# esp8266_env.net
KiCad netlist of a schematic drawn in EAGLE
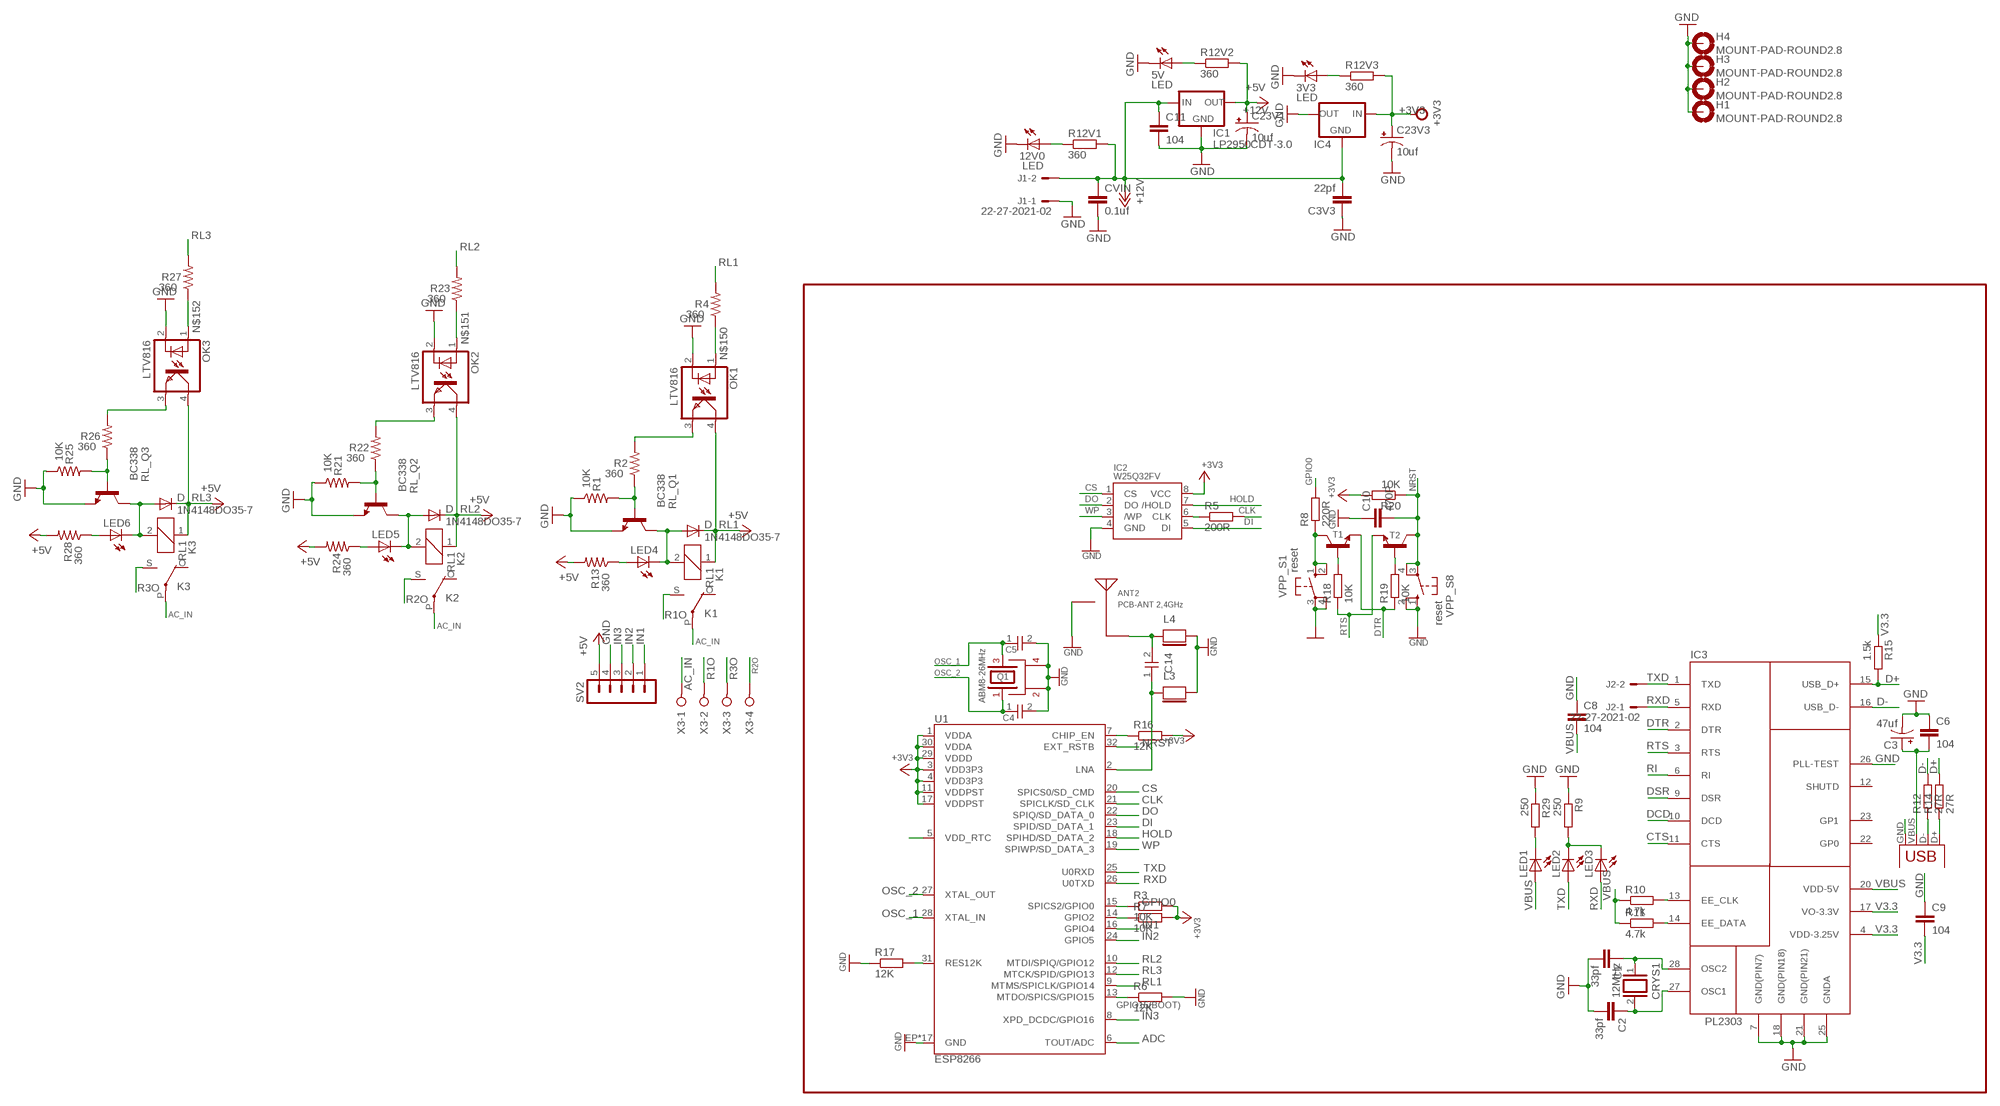
[diagram p0: schematic, sheet 1]

(export (version "E")
  (design (tool "Eeschema 10.0.6"))
  (components
    (comp (ref "3V3")
      (value "LED")
      (footprint "eagle-import:SML0805")
      (libsource (lib "eagle-import") (part "LEDSML0805"))
    )
    (comp (ref "5V")
      (value "LED")
      (footprint "eagle-import:SML0805")
      (libsource (lib "eagle-import") (part "LEDSML0805"))
    )
    (comp (ref "12V0")
      (value "LED")
      (footprint "eagle-import:SML0805")
      (libsource (lib "eagle-import") (part "LEDSML0805"))
    )
    (comp (ref "ANT2")
      (value "PCB-ANT 2,4GHz")
      (footprint "eagle-import:2.4GHZ_PCB")
      (libsource (lib "eagle-import") (part "2.4GHZ_PCB"))
    )
    (comp (ref "C1")
      (value "33pf")
      (footprint "eagle-import:C0805")
      (libsource (lib "eagle-import") (part "C-EUC0805"))
    )
    (comp (ref "C2")
      (value "33pf")
      (footprint "eagle-import:C0805")
      (libsource (lib "eagle-import") (part "C-EUC0805"))
    )
    (comp (ref "C3")
      (value "47uf")
      (footprint "eagle-import:E2,5-5")
      (libsource (lib "eagle-import") (part "CPOL-USE2.5-5"))
    )
    (comp (ref "C3V3")
      (value "22pf")
      (footprint "eagle-import:C0805")
      (libsource (lib "eagle-import") (part "C-EUC0805"))
    )
    (comp (ref "C4")
      (value "10P-50VCOG_0603")
      (footprint "eagle-import:C0603")
      (libsource (lib "eagle-import") (part "COG?_060310P-50V"))
    )
    (comp (ref "C5")
      (value "10P-50VCOG_0603")
      (footprint "eagle-import:C0603")
      (libsource (lib "eagle-import") (part "COG?_060310P-50V"))
    )
    (comp (ref "C6")
      (value "104")
      (footprint "eagle-import:C0805")
      (libsource (lib "eagle-import") (part "C-EUC0805"))
    )
    (comp (ref "C8")
      (value "104")
      (footprint "eagle-import:C0805")
      (libsource (lib "eagle-import") (part "C-EUC0805"))
    )
    (comp (ref "C9")
      (value "104")
      (footprint "eagle-import:C0805")
      (libsource (lib "eagle-import") (part "C-EUC0805"))
    )
    (comp (ref "C10")
      (value "470P")
      (footprint "eagle-import:C0805")
      (libsource (lib "eagle-import") (part "C-EUC0805"))
    )
    (comp (ref "C11")
      (value "104")
      (footprint "eagle-import:C0805")
      (libsource (lib "eagle-import") (part "C-EUC0805"))
    )
    (comp (ref "C14")
      (value "5.6pF")
      (footprint "eagle-import:C0402")
      (libsource (lib "eagle-import") (part "CC0402"))
    )
    (comp (ref "C23V1")
      (value "10uf")
      (footprint "eagle-import:E2,5-5")
      (libsource (lib "eagle-import") (part "CPOL-USE2.5-5"))
    )
    (comp (ref "C23V3")
      (value "10uf")
      (footprint "eagle-import:E2,5-5")
      (libsource (lib "eagle-import") (part "CPOL-USE2.5-5"))
    )
    (comp (ref "CRYS1")
      (value "12MHz")
      (footprint "eagle-import:QS")
      (libsource (lib "eagle-import") (part "XTAL/S"))
    )
    (comp (ref "CVIN")
      (value "0.1uf")
      (footprint "eagle-import:C0805")
      (libsource (lib "eagle-import") (part "C-EUC0805"))
    )
    (comp (ref "D_RL1")
      (value "1N4148DO35-7")
      (footprint "eagle-import:DO35-7")
      (libsource (lib "eagle-import") (part "1N4148DO35-7"))
    )
    (comp (ref "D_RL2")
      (value "1N4148DO35-7")
      (footprint "eagle-import:DO35-7")
      (libsource (lib "eagle-import") (part "1N4148DO35-7"))
    )
    (comp (ref "D_RL3")
      (value "1N4148DO35-7")
      (footprint "eagle-import:DO35-7")
      (libsource (lib "eagle-import") (part "1N4148DO35-7"))
    )
    (comp (ref "H1")
      (value "MOUNT-PAD-ROUND2.8")
      (footprint "eagle-import:2,8-PAD")
      (libsource (lib "eagle-import") (part "MOUNT-PAD-ROUND2.8"))
    )
    (comp (ref "H2")
      (value "MOUNT-PAD-ROUND2.8")
      (footprint "eagle-import:2,8-PAD")
      (libsource (lib "eagle-import") (part "MOUNT-PAD-ROUND2.8"))
    )
    (comp (ref "H3")
      (value "MOUNT-PAD-ROUND2.8")
      (footprint "eagle-import:2,8-PAD")
      (libsource (lib "eagle-import") (part "MOUNT-PAD-ROUND2.8"))
    )
    (comp (ref "H4")
      (value "MOUNT-PAD-ROUND2.8")
      (footprint "eagle-import:2,8-PAD")
      (libsource (lib "eagle-import") (part "MOUNT-PAD-ROUND2.8"))
    )
    (comp (ref "IC1")
      (value "LP2950CDT-3.0")
      (footprint "eagle-import:DPACK")
      (libsource (lib "eagle-import") (part "LP2950?CDT-3.0"))
    )
    (comp (ref "IC2")
      (value "W25Q32FV")
      (footprint "eagle-import:SOIC-8_208MIL")
      (libsource (lib "eagle-import") (part "W25Q32FV"))
    )
    (comp (ref "IC3")
      (value "PL2303")
      (footprint "eagle-import:SSOP28")
      (libsource (lib "eagle-import") (part "PL2303"))
    )
    (comp (ref "IC4")
      (value "LM1117")
      (footprint "eagle-import:SOT223")
      (libsource (lib "eagle-import") (part "LM1117"))
    )
    (comp (ref "J1")
      (value "22-27-2021-02")
      (footprint "eagle-import:6410-02")
      (libsource (lib "eagle-import") (part "22-?-0227-2021"))
    )
    (comp (ref "J2")
      (value "22-27-2021-02")
      (footprint "eagle-import:6410-02")
      (libsource (lib "eagle-import") (part "22-?-0227-2021"))
    )
    (comp (ref "K1")
      (value "RL1")
      (footprint "eagle-import:G5LE")
      (libsource (lib "eagle-import") (part "G5L"))
    )
    (comp (ref "K2")
      (value "RL1")
      (footprint "eagle-import:G5LE")
      (libsource (lib "eagle-import") (part "G5L"))
    )
    (comp (ref "K3")
      (value "RL1")
      (footprint "eagle-import:G5LE")
      (libsource (lib "eagle-import") (part "G5L"))
    )
    (comp (ref "L3")
      (value "NC")
      (footprint "eagle-import:L0402")
      (libsource (lib "eagle-import") (part "LL0402"))
    )
    (comp (ref "L4")
      (value "NC")
      (footprint "eagle-import:L0402")
      (libsource (lib "eagle-import") (part "LL0402"))
    )
    (comp (ref "LED1")
      (value "LEDSML0805")
      (footprint "eagle-import:SML0805")
      (libsource (lib "eagle-import") (part "LEDSML0805"))
    )
    (comp (ref "LED2")
      (value "LEDSML0805")
      (footprint "eagle-import:SML0805")
      (libsource (lib "eagle-import") (part "LEDSML0805"))
    )
    (comp (ref "LED3")
      (value "LEDSML0805")
      (footprint "eagle-import:SML0805")
      (libsource (lib "eagle-import") (part "LEDSML0805"))
    )
    (comp (ref "LED4")
      (value "LEDSML0805")
      (footprint "eagle-import:SML0805")
      (libsource (lib "eagle-import") (part "LEDSML0805"))
    )
    (comp (ref "LED5")
      (value "LEDSML0805")
      (footprint "eagle-import:SML0805")
      (libsource (lib "eagle-import") (part "LEDSML0805"))
    )
    (comp (ref "LED6")
      (value "LEDSML0805")
      (footprint "eagle-import:SML0805")
      (libsource (lib "eagle-import") (part "LEDSML0805"))
    )
    (comp (ref "OK1")
      (value "LTV816")
      (footprint "eagle-import:DIL04")
      (libsource (lib "eagle-import") (part "LTV816"))
    )
    (comp (ref "OK2")
      (value "LTV816")
      (footprint "eagle-import:DIL04")
      (libsource (lib "eagle-import") (part "LTV816"))
    )
    (comp (ref "OK3")
      (value "LTV816")
      (footprint "eagle-import:DIL04")
      (libsource (lib "eagle-import") (part "LTV816"))
    )
    (comp (ref "Q1")
      (value "ABM8-26MHz")
      (footprint "eagle-import:ABM8G")
      (libsource (lib "eagle-import") (part "ABM8G"))
    )
    (comp (ref "R1")
      (value "10K")
      (footprint "eagle-import:0805")
      (libsource (lib "eagle-import") (part "RESISTOR0805-RES"))
    )
    (comp (ref "R2")
      (value "360")
      (footprint "eagle-import:0805")
      (libsource (lib "eagle-import") (part "RESISTOR0805-RES"))
    )
    (comp (ref "R3")
      (value "10K")
      (footprint "eagle-import:M0805")
      (libsource (lib "eagle-import") (part "R-EU_M0805"))
    )
    (comp (ref "R4")
      (value "360")
      (footprint "eagle-import:0805")
      (libsource (lib "eagle-import") (part "RESISTOR0805-RES"))
    )
    (comp (ref "R5")
      (value "200R")
      (footprint "eagle-import:M0805")
      (libsource (lib "eagle-import") (part "R-EU_M0805"))
    )
    (comp (ref "R6")
      (value "12K")
      (footprint "eagle-import:M0805")
      (libsource (lib "eagle-import") (part "R-EU_M0805"))
    )
    (comp (ref "R7")
      (value "10K")
      (footprint "eagle-import:M0805")
      (libsource (lib "eagle-import") (part "R-EU_M0805"))
    )
    (comp (ref "R8")
      (value "220R")
      (footprint "eagle-import:M0805")
      (libsource (lib "eagle-import") (part "R-EU_M0805"))
    )
    (comp (ref "R9")
      (value "250")
      (footprint "eagle-import:R0805")
      (libsource (lib "eagle-import") (part "R-EU_R0805"))
    )
    (comp (ref "R10")
      (value "4.7k")
      (footprint "eagle-import:M0805")
      (libsource (lib "eagle-import") (part "R-EU_M0805"))
    )
    (comp (ref "R11")
      (value "4.7k")
      (footprint "eagle-import:M0805")
      (libsource (lib "eagle-import") (part "R-EU_M0805"))
    )
    (comp (ref "R12")
      (value "27R")
      (footprint "eagle-import:R0805")
      (libsource (lib "eagle-import") (part "R-EU_R0805"))
    )
    (comp (ref "R12V1")
      (value "360")
      (footprint "eagle-import:R0805")
      (libsource (lib "eagle-import") (part "R-EU_R0805"))
    )
    (comp (ref "R12V2")
      (value "360")
      (footprint "eagle-import:R0805")
      (libsource (lib "eagle-import") (part "R-EU_R0805"))
    )
    (comp (ref "R12V3")
      (value "360")
      (footprint "eagle-import:R0805")
      (libsource (lib "eagle-import") (part "R-EU_R0805"))
    )
    (comp (ref "R13")
      (value "360")
      (footprint "eagle-import:0805")
      (libsource (lib "eagle-import") (part "RESISTOR0805-RES"))
    )
    (comp (ref "R14")
      (value "27R")
      (footprint "eagle-import:R0805")
      (libsource (lib "eagle-import") (part "R-EU_R0805"))
    )
    (comp (ref "R15")
      (value "1.5k")
      (footprint "eagle-import:R0805")
      (libsource (lib "eagle-import") (part "R-EU_R0805"))
    )
    (comp (ref "R16")
      (value "12K")
      (footprint "eagle-import:M0805")
      (libsource (lib "eagle-import") (part "R-EU_M0805"))
    )
    (comp (ref "R17")
      (value "12K")
      (footprint "eagle-import:M0805")
      (fields (field (name "SPICEPREFIX") "R"))
      (libsource (lib "eagle-import") (part "R-EU_M0805"))
    )
    (comp (ref "R18")
      (value "10K")
      (footprint "eagle-import:M0805")
      (libsource (lib "eagle-import") (part "R-EU_M0805"))
    )
    (comp (ref "R19")
      (value "10K")
      (footprint "eagle-import:M0805")
      (libsource (lib "eagle-import") (part "R-EU_M0805"))
    )
    (comp (ref "R20")
      (value "10K")
      (footprint "eagle-import:M0805")
      (libsource (lib "eagle-import") (part "R-EU_M0805"))
    )
    (comp (ref "R21")
      (value "10K")
      (footprint "eagle-import:0805")
      (libsource (lib "eagle-import") (part "RESISTOR0805-RES"))
    )
    (comp (ref "R22")
      (value "360")
      (footprint "eagle-import:0805")
      (libsource (lib "eagle-import") (part "RESISTOR0805-RES"))
    )
    (comp (ref "R23")
      (value "360")
      (footprint "eagle-import:0805")
      (libsource (lib "eagle-import") (part "RESISTOR0805-RES"))
    )
    (comp (ref "R24")
      (value "360")
      (footprint "eagle-import:0805")
      (libsource (lib "eagle-import") (part "RESISTOR0805-RES"))
    )
    (comp (ref "R25")
      (value "10K")
      (footprint "eagle-import:0805")
      (libsource (lib "eagle-import") (part "RESISTOR0805-RES"))
    )
    (comp (ref "R26")
      (value "360")
      (footprint "eagle-import:0805")
      (libsource (lib "eagle-import") (part "RESISTOR0805-RES"))
    )
    (comp (ref "R27")
      (value "360")
      (footprint "eagle-import:0805")
      (libsource (lib "eagle-import") (part "RESISTOR0805-RES"))
    )
    (comp (ref "R28")
      (value "360")
      (footprint "eagle-import:0805")
      (libsource (lib "eagle-import") (part "RESISTOR0805-RES"))
    )
    (comp (ref "R29")
      (value "250")
      (footprint "eagle-import:R0805")
      (libsource (lib "eagle-import") (part "R-EU_R0805"))
    )
    (comp (ref "RL_Q1")
      (value "BC338")
      (footprint "eagle-import:TO92-EBC")
      (libsource (lib "eagle-import") (part "BC338"))
    )
    (comp (ref "RL_Q2")
      (value "BC338")
      (footprint "eagle-import:TO92-EBC")
      (libsource (lib "eagle-import") (part "BC338"))
    )
    (comp (ref "RL_Q3")
      (value "BC338")
      (footprint "eagle-import:TO92-EBC")
      (libsource (lib "eagle-import") (part "BC338"))
    )
    (comp (ref "SV2")
      (value "MA05-1")
      (footprint "eagle-import:MA05-1")
      (libsource (lib "eagle-import") (part "MA05-1"))
    )
    (comp (ref "T1")
      (value "BC817-NPN-SOT23-BEC")
      (footprint "eagle-import:SOT23-BEC")
      (libsource (lib "eagle-import") (part "-NPN-SOT23-BECBC817"))
    )
    (comp (ref "T2")
      (value "BC817-NPN-SOT23-BEC")
      (footprint "eagle-import:SOT23-BEC")
      (libsource (lib "eagle-import") (part "-NPN-SOT23-BECBC817"))
    )
    (comp (ref "U1")
      (value "ESP8266")
      (footprint "eagle-import:QFN32-5X5MM")
      (fields (field (name "MF") "Espressif Systems"))
      (libsource (lib "eagle-import") (part "ESP8266"))
    )
    (comp (ref "VPP_S1")
      (value "reset")
      (footprint "eagle-import:B3F-10XX")
      (fields (field (name "MPN") "B3F-1000"))
      (libsource (lib "eagle-import") (part "10-XX"))
    )
    (comp (ref "VPP_S8")
      (value "reset")
      (footprint "eagle-import:B3F-10XX")
      (fields (field (name "MPN") "B3F-1000"))
      (libsource (lib "eagle-import") (part "10-XX"))
    )
    (comp (ref "X1")
      (value "USB-MICROB")
      (footprint "eagle-import:USB-MICROB")
      (libsource (lib "eagle-import") (part "USB-MICROB"))
    )
    (comp (ref "X3")
      (value "W237-04P")
      (footprint "eagle-import:W237-4P")
      (libsource (lib "eagle-import") (part "W237-04P"))
    )
  )
  (nets
    (net (code "1") (name "+3V3") (class "Default")
      (node (ref "C23V3") (pin "+") (pinfunction "+_+") (pintype "passive"))
      (node (ref "IC2") (pin "8") (pinfunction "VCC_8") (pintype "bidirectional"))
      (node (ref "IC4") (pin "3") (pinfunction "IN_3") (pintype "input"))
      (node (ref "R12V3") (pin "2") (pinfunction "2_2") (pintype "passive"))
      (node (ref "R16") (pin "2") (pinfunction "2_2") (pintype "passive"))
      (node (ref "R20") (pin "2") (pinfunction "2_2") (pintype "passive"))
      (node (ref "R3") (pin "2") (pinfunction "2_2") (pintype "passive"))
      (node (ref "R7") (pin "2") (pinfunction "2_2") (pintype "passive"))
      (node (ref "U1") (pin "1") (pinfunction "VDDA_1") (pintype "bidirectional"))
      (node (ref "U1") (pin "11") (pinfunction "VDDPST_11") (pintype "bidirectional"))
      (node (ref "U1") (pin "17") (pinfunction "VDDPST_17") (pintype "bidirectional"))
      (node (ref "U1") (pin "29") (pinfunction "VDDD_29") (pintype "bidirectional"))
      (node (ref "U1") (pin "3") (pinfunction "VDD3P3_3") (pintype "bidirectional"))
      (node (ref "U1") (pin "30") (pinfunction "VDDA_30") (pintype "bidirectional"))
      (node (ref "U1") (pin "4") (pinfunction "VDD3P3_4") (pintype "bidirectional"))
    )
    (net (code "2") (name "+5V") (class "Default")
      (node (ref "C23V1") (pin "+") (pinfunction "+_+") (pintype "passive"))
      (node (ref "D_RL1") (pin "C") (pinfunction "C_C") (pintype "passive"))
      (node (ref "D_RL2") (pin "C") (pinfunction "C_C") (pintype "passive"))
      (node (ref "D_RL3") (pin "C") (pinfunction "C_C") (pintype "passive"))
      (node (ref "IC1") (pin "3") (pinfunction "OUT_3") (pintype "passive"))
      (node (ref "K1") (pin "1") (pinfunction "1_1") (pintype "passive"))
      (node (ref "K2") (pin "1") (pinfunction "1_1") (pintype "passive"))
      (node (ref "K3") (pin "1") (pinfunction "1_1") (pintype "passive"))
      (node (ref "OK1") (pin "4") (pinfunction "COL_4") (pintype "passive"))
      (node (ref "OK2") (pin "4") (pinfunction "COL_4") (pintype "passive"))
      (node (ref "OK3") (pin "4") (pinfunction "COL_4") (pintype "passive"))
      (node (ref "R12V2") (pin "2") (pinfunction "2_2") (pintype "passive"))
      (node (ref "R13") (pin "2") (pinfunction "2_2") (pintype "passive"))
      (node (ref "R24") (pin "2") (pinfunction "2_2") (pintype "passive"))
      (node (ref "R28") (pin "2") (pinfunction "2_2") (pintype "passive"))
      (node (ref "SV2") (pin "5") (pinfunction "5_5") (pintype "passive"))
    )
    (net (code "3") (name "+12V") (class "Default")
      (node (ref "C11") (pin "1") (pinfunction "1_1") (pintype "passive"))
      (node (ref "C3V3") (pin "2") (pinfunction "2_2") (pintype "passive"))
      (node (ref "CVIN") (pin "1") (pinfunction "1_1") (pintype "passive"))
      (node (ref "IC1") (pin "1") (pinfunction "IN_1") (pintype "input"))
      (node (ref "IC4") (pin "1") (pinfunction "GND_1") (pintype "input"))
      (node (ref "J1") (pin "2") (pinfunction "S_2") (pintype "passive"))
      (node (ref "R12V1") (pin "2") (pinfunction "2_2") (pintype "passive"))
    )
    (net (code "4") (name "/AC_IN") (class "Default")
      (node (ref "K1") (pin "P") (pinfunction "P_P") (pintype "passive"))
      (node (ref "K2") (pin "P") (pinfunction "P_P") (pintype "passive"))
      (node (ref "K3") (pin "P") (pinfunction "P_P") (pintype "passive"))
      (node (ref "X3") (pin "1") (pinfunction "KL_1") (pintype "passive"))
    )
    (net (code "5") (name "/ADC") (class "Default")
      (node (ref "U1") (pin "6") (pinfunction "TOUT/ADC_6") (pintype "bidirectional"))
    )
    (net (code "6") (name "/CLK") (class "Default")
      (node (ref "R5") (pin "2") (pinfunction "2_2") (pintype "passive"))
      (node (ref "U1") (pin "21") (pinfunction "SPICLK/SD_CLK_21") (pintype "bidirectional"))
    )
    (net (code "7") (name "/CS") (class "Default")
      (node (ref "IC2") (pin "1") (pinfunction "CS_1") (pintype "bidirectional"))
      (node (ref "U1") (pin "20") (pinfunction "SPICS0/SD_CMD_20") (pintype "bidirectional"))
    )
    (net (code "8") (name "/CTS") (class "Default")
      (node (ref "IC3") (pin "11") (pinfunction "CTS_11") (pintype "bidirectional"))
    )
    (net (code "9") (name "/D+") (class "Default")
      (node (ref "IC3") (pin "15") (pinfunction "USB_D+_15") (pintype "bidirectional"))
      (node (ref "R14") (pin "2") (pinfunction "2_2") (pintype "passive"))
      (node (ref "R15") (pin "2") (pinfunction "2_2") (pintype "passive"))
    )
    (net (code "10") (name "/D-") (class "Default")
      (node (ref "IC3") (pin "16") (pinfunction "USB_D-_16") (pintype "bidirectional"))
      (node (ref "R12") (pin "2") (pinfunction "2_2") (pintype "passive"))
    )
    (net (code "11") (name "/DCD") (class "Default")
      (node (ref "IC3") (pin "10") (pinfunction "DCD_10") (pintype "bidirectional"))
    )
    (net (code "12") (name "/DI") (class "Default")
      (node (ref "IC2") (pin "5") (pinfunction "DI_5") (pintype "bidirectional"))
      (node (ref "U1") (pin "23") (pinfunction "SPID/SD_DATA_1_23") (pintype "bidirectional"))
    )
    (net (code "13") (name "/DO") (class "Default")
      (node (ref "IC2") (pin "2") (pinfunction "DO_2") (pintype "bidirectional"))
      (node (ref "U1") (pin "22") (pinfunction "SPIQ/SD_DATA_0_22") (pintype "bidirectional"))
    )
    (net (code "14") (name "/DSR") (class "Default")
      (node (ref "IC3") (pin "9") (pinfunction "DSR_9") (pintype "bidirectional"))
    )
    (net (code "15") (name "/DTR") (class "Default")
      (node (ref "IC3") (pin "2") (pinfunction "DTR_2") (pintype "bidirectional"))
      (node (ref "R19") (pin "1") (pinfunction "1_1") (pintype "passive"))
      (node (ref "T1") (pin "E") (pinfunction "E_E") (pintype "passive"))
    )
    (net (code "16") (name "/GPIO0") (class "Default")
      (node (ref "R3") (pin "1") (pinfunction "1_1") (pintype "passive"))
      (node (ref "R8") (pin "2") (pinfunction "2_2") (pintype "passive"))
      (node (ref "U1") (pin "15") (pinfunction "SPICS2/GPIO0_15") (pintype "bidirectional"))
    )
    (net (code "17") (name "/HOLD") (class "Default")
      (node (ref "IC2") (pin "7") (pinfunction "/HOLD_7") (pintype "bidirectional"))
      (node (ref "U1") (pin "18") (pinfunction "SPIHD/SD_DATA_2_18") (pintype "bidirectional"))
    )
    (net (code "18") (name "/IN1") (class "Default")
      (node (ref "SV2") (pin "1") (pinfunction "1_1") (pintype "passive"))
      (node (ref "U1") (pin "16") (pinfunction "GPIO4_16") (pintype "bidirectional"))
    )
    (net (code "19") (name "/IN2") (class "Default")
      (node (ref "SV2") (pin "2") (pinfunction "2_2") (pintype "passive"))
      (node (ref "U1") (pin "24") (pinfunction "GPIO5_24") (pintype "bidirectional"))
    )
    (net (code "20") (name "/IN3") (class "Default")
      (node (ref "SV2") (pin "3") (pinfunction "3_3") (pintype "passive"))
      (node (ref "U1") (pin "8") (pinfunction "XPD_DCDC/GPIO16_8") (pintype "bidirectional"))
    )
    (net (code "21") (name "/N$150") (class "Default")
      (node (ref "OK1") (pin "1") (pinfunction "A_1") (pintype "passive"))
      (node (ref "R4") (pin "1") (pinfunction "1_1") (pintype "passive"))
    )
    (net (code "22") (name "/N$151") (class "Default")
      (node (ref "OK2") (pin "1") (pinfunction "A_1") (pintype "passive"))
      (node (ref "R23") (pin "1") (pinfunction "1_1") (pintype "passive"))
    )
    (net (code "23") (name "/N$152") (class "Default")
      (node (ref "OK3") (pin "1") (pinfunction "A_1") (pintype "passive"))
      (node (ref "R27") (pin "1") (pinfunction "1_1") (pintype "passive"))
    )
    (net (code "24") (name "/NRST") (class "Default")
      (node (ref "C10") (pin "2") (pinfunction "2_2") (pintype "passive"))
      (node (ref "R20") (pin "1") (pinfunction "1_1") (pintype "passive"))
      (node (ref "T2") (pin "C") (pinfunction "C_C") (pintype "passive"))
      (node (ref "U1") (pin "32") (pinfunction "EXT_RSTB_32") (pintype "bidirectional"))
      (node (ref "VPP_S8") (pin "3") (pinfunction "P_3") (pintype "passive"))
      (node (ref "VPP_S8") (pin "4") (pinfunction "P1_4") (pintype "passive"))
    )
    (net (code "25") (name "/OSC_1") (class "Default")
      (node (ref "C5") (pin "1") (pinfunction "C_1") (pintype "passive"))
      (node (ref "Q1") (pin "3") (pinfunction "3_3") (pintype "passive"))
      (node (ref "U1") (pin "28") (pinfunction "XTAL_IN_28") (pintype "bidirectional"))
    )
    (net (code "26") (name "/OSC_2") (class "Default")
      (node (ref "C4") (pin "1") (pinfunction "C_1") (pintype "passive"))
      (node (ref "Q1") (pin "1") (pinfunction "1_1") (pintype "passive"))
      (node (ref "U1") (pin "27") (pinfunction "XTAL_OUT_27") (pintype "bidirectional"))
    )
    (net (code "27") (name "/R1O") (class "Default")
      (node (ref "K1") (pin "S") (pinfunction "S_S") (pintype "passive"))
      (node (ref "X3") (pin "2") (pinfunction "KL_2") (pintype "passive"))
    )
    (net (code "28") (name "/R2O") (class "Default")
      (node (ref "K2") (pin "S") (pinfunction "S_S") (pintype "passive"))
      (node (ref "X3") (pin "4") (pinfunction "KL_4") (pintype "passive"))
    )
    (net (code "29") (name "/R3O") (class "Default")
      (node (ref "K3") (pin "S") (pinfunction "S_S") (pintype "passive"))
      (node (ref "X3") (pin "3") (pinfunction "KL_3") (pintype "passive"))
    )
    (net (code "30") (name "/RI") (class "Default")
      (node (ref "IC3") (pin "6") (pinfunction "RI_6") (pintype "bidirectional"))
    )
    (net (code "31") (name "/RL1") (class "Default")
      (node (ref "R4") (pin "2") (pinfunction "2_2") (pintype "passive"))
      (node (ref "U1") (pin "9") (pinfunction "MTMS/SPICLK/GPIO14_9") (pintype "bidirectional"))
    )
    (net (code "32") (name "/RL2") (class "Default")
      (node (ref "R23") (pin "2") (pinfunction "2_2") (pintype "passive"))
      (node (ref "U1") (pin "10") (pinfunction "MTDI/SPIQ/GPIO12_10") (pintype "bidirectional"))
    )
    (net (code "33") (name "/RL3") (class "Default")
      (node (ref "R27") (pin "2") (pinfunction "2_2") (pintype "passive"))
      (node (ref "U1") (pin "12") (pinfunction "MTCK/SPID/GPIO13_12") (pintype "bidirectional"))
    )
    (net (code "34") (name "/RTS") (class "Default")
      (node (ref "IC3") (pin "3") (pinfunction "RTS_3") (pintype "bidirectional"))
      (node (ref "R18") (pin "1") (pinfunction "1_1") (pintype "passive"))
      (node (ref "T2") (pin "E") (pinfunction "E_E") (pintype "passive"))
    )
    (net (code "35") (name "/RXD") (class "Default")
      (node (ref "IC3") (pin "5") (pinfunction "RXD_5") (pintype "bidirectional"))
      (node (ref "J2") (pin "1") (pinfunction "S_1") (pintype "passive"))
      (node (ref "LED3") (pin "A") (pinfunction "A_A") (pintype "passive"))
      (node (ref "U1") (pin "26") (pinfunction "U0TXD_26") (pintype "bidirectional"))
    )
    (net (code "36") (name "/TXD") (class "Default")
      (node (ref "IC3") (pin "1") (pinfunction "TXD_1") (pintype "bidirectional"))
      (node (ref "J2") (pin "2") (pinfunction "S_2") (pintype "passive"))
      (node (ref "LED2") (pin "A") (pinfunction "A_A") (pintype "passive"))
      (node (ref "U1") (pin "25") (pinfunction "U0RXD_25") (pintype "bidirectional"))
    )
    (net (code "37") (name "/V3.3") (class "Default")
      (node (ref "C9") (pin "2") (pinfunction "2_2") (pintype "passive"))
      (node (ref "IC3") (pin "17") (pinfunction "VO-3.3V_17") (pintype "bidirectional"))
      (node (ref "IC3") (pin "4") (pinfunction "VDD-3.25V_4") (pintype "bidirectional"))
      (node (ref "R15") (pin "1") (pinfunction "1_1") (pintype "passive"))
    )
    (net (code "38") (name "/VBUS") (class "Default")
      (node (ref "C3") (pin "+") (pinfunction "+_+") (pintype "passive"))
      (node (ref "C6") (pin "2") (pinfunction "2_2") (pintype "passive"))
      (node (ref "C8") (pin "2") (pinfunction "2_2") (pintype "passive"))
      (node (ref "IC3") (pin "20") (pinfunction "VDD-5V_20") (pintype "bidirectional"))
      (node (ref "LED1") (pin "A") (pinfunction "A_A") (pintype "passive"))
      (node (ref "R10") (pin "1") (pinfunction "1_1") (pintype "passive"))
      (node (ref "R11") (pin "1") (pinfunction "1_1") (pintype "passive"))
      (node (ref "X1") (pin "VBUS") (pinfunction "VBUS_VBUS") (pintype "bidirectional"))
    )
    (net (code "39") (name "/WP") (class "Default")
      (node (ref "IC2") (pin "3") (pinfunction "/WP_3") (pintype "bidirectional"))
      (node (ref "U1") (pin "19") (pinfunction "SPIWP/SD_DATA_3_19") (pintype "bidirectional"))
    )
    (net (code "40") (name "GND") (class "Default")
      (node (ref "12V0") (pin "C") (pinfunction "C_C") (pintype "passive"))
      (node (ref "3V3") (pin "C") (pinfunction "C_C") (pintype "passive"))
      (node (ref "5V") (pin "C") (pinfunction "C_C") (pintype "passive"))
      (node (ref "ANT2") (pin "GND") (pinfunction "2_GND") (pintype "bidirectional"))
      (node (ref "C1") (pin "2") (pinfunction "2_2") (pintype "passive"))
      (node (ref "C10") (pin "1") (pinfunction "1_1") (pintype "passive"))
      (node (ref "C11") (pin "2") (pinfunction "2_2") (pintype "passive"))
      (node (ref "C2") (pin "2") (pinfunction "2_2") (pintype "passive"))
      (node (ref "C23V1") (pin "-") (pinfunction "-_-") (pintype "passive"))
      (node (ref "C23V3") (pin "-") (pinfunction "-_-") (pintype "passive"))
      (node (ref "C3") (pin "-") (pinfunction "-_-") (pintype "passive"))
      (node (ref "C3V3") (pin "1") (pinfunction "1_1") (pintype "passive"))
      (node (ref "C4") (pin "2") (pinfunction "C_2") (pintype "passive"))
      (node (ref "C5") (pin "2") (pinfunction "C_2") (pintype "passive"))
      (node (ref "C6") (pin "1") (pinfunction "1_1") (pintype "passive"))
      (node (ref "C8") (pin "1") (pinfunction "1_1") (pintype "passive"))
      (node (ref "C9") (pin "1") (pinfunction "1_1") (pintype "passive"))
      (node (ref "CVIN") (pin "2") (pinfunction "2_2") (pintype "passive"))
      (node (ref "H1") (pin "B2,8") (pinfunction "MOUNT_B2,8") (pintype "passive"))
      (node (ref "H2") (pin "B2,8") (pinfunction "MOUNT_B2,8") (pintype "passive"))
      (node (ref "H3") (pin "B2,8") (pinfunction "MOUNT_B2,8") (pintype "passive"))
      (node (ref "H4") (pin "B2,8") (pinfunction "MOUNT_B2,8") (pintype "passive"))
      (node (ref "IC1") (pin "4") (pinfunction "GND_4") (pintype "input"))
      (node (ref "IC2") (pin "4") (pinfunction "GND_4") (pintype "bidirectional"))
      (node (ref "IC3") (pin "18") (pinfunction "GND(PIN18)_18") (pintype "bidirectional"))
      (node (ref "IC3") (pin "21") (pinfunction "GND(PIN21)_21") (pintype "bidirectional"))
      (node (ref "IC3") (pin "25") (pinfunction "GNDA_25") (pintype "bidirectional"))
      (node (ref "IC3") (pin "26") (pinfunction "PLL-TEST_26") (pintype "bidirectional"))
      (node (ref "IC3") (pin "7") (pinfunction "GND(PIN7)_7") (pintype "bidirectional"))
      (node (ref "IC4") (pin "2") (pinfunction "OUT_2") (pintype "passive"))
      (node (ref "J1") (pin "1") (pinfunction "S_1") (pintype "passive"))
      (node (ref "L3") (pin "2") (pinfunction "L_2") (pintype "passive"))
      (node (ref "L4") (pin "2") (pinfunction "L_2") (pintype "passive"))
      (node (ref "OK1") (pin "2") (pinfunction "C_2") (pintype "passive"))
      (node (ref "OK2") (pin "2") (pinfunction "C_2") (pintype "passive"))
      (node (ref "OK3") (pin "2") (pinfunction "C_2") (pintype "passive"))
      (node (ref "Q1") (pin "2") (pinfunction "2_2") (pintype "bidirectional"))
      (node (ref "Q1") (pin "4") (pinfunction "4_4") (pintype "bidirectional"))
      (node (ref "R1") (pin "1") (pinfunction "1_1") (pintype "passive"))
      (node (ref "R17") (pin "1") (pinfunction "1_1") (pintype "passive"))
      (node (ref "R21") (pin "1") (pinfunction "1_1") (pintype "passive"))
      (node (ref "R25") (pin "1") (pinfunction "1_1") (pintype "passive"))
      (node (ref "R29") (pin "1") (pinfunction "1_1") (pintype "passive"))
      (node (ref "R6") (pin "2") (pinfunction "2_2") (pintype "passive"))
      (node (ref "R9") (pin "1") (pinfunction "1_1") (pintype "passive"))
      (node (ref "RL_Q1") (pin "E") (pinfunction "E_E") (pintype "passive"))
      (node (ref "RL_Q2") (pin "E") (pinfunction "E_E") (pintype "passive"))
      (node (ref "RL_Q3") (pin "E") (pinfunction "E_E") (pintype "passive"))
      (node (ref "SV2") (pin "4") (pinfunction "4_4") (pintype "passive"))
      (node (ref "U1") (pin "EP") (pinfunction "GND_EP") (pintype "bidirectional"))
      (node (ref "U1") (pin "P$1") (pinfunction "GND_P$1") (pintype "bidirectional"))
      (node (ref "U1") (pin "P$10") (pinfunction "GND_P$10") (pintype "bidirectional"))
      (node (ref "U1") (pin "P$11") (pinfunction "GND_P$11") (pintype "bidirectional"))
      (node (ref "U1") (pin "P$12") (pinfunction "GND_P$12") (pintype "bidirectional"))
      (node (ref "U1") (pin "P$13") (pinfunction "GND_P$13") (pintype "bidirectional"))
      (node (ref "U1") (pin "P$14") (pinfunction "GND_P$14") (pintype "bidirectional"))
      (node (ref "U1") (pin "P$15") (pinfunction "GND_P$15") (pintype "bidirectional"))
      (node (ref "U1") (pin "P$16") (pinfunction "GND_P$16") (pintype "bidirectional"))
      (node (ref "U1") (pin "P$2") (pinfunction "GND_P$2") (pintype "bidirectional"))
      (node (ref "U1") (pin "P$3") (pinfunction "GND_P$3") (pintype "bidirectional"))
      (node (ref "U1") (pin "P$4") (pinfunction "GND_P$4") (pintype "bidirectional"))
      (node (ref "U1") (pin "P$5") (pinfunction "GND_P$5") (pintype "bidirectional"))
      (node (ref "U1") (pin "P$6") (pinfunction "GND_P$6") (pintype "bidirectional"))
      (node (ref "U1") (pin "P$7") (pinfunction "GND_P$7") (pintype "bidirectional"))
      (node (ref "U1") (pin "P$8") (pinfunction "GND_P$8") (pintype "bidirectional"))
      (node (ref "U1") (pin "P$9") (pinfunction "GND_P$9") (pintype "bidirectional"))
      (node (ref "VPP_S1") (pin "3") (pinfunction "P_3") (pintype "passive"))
      (node (ref "VPP_S1") (pin "4") (pinfunction "P1_4") (pintype "passive"))
      (node (ref "VPP_S8") (pin "1") (pinfunction "S_1") (pintype "passive"))
      (node (ref "VPP_S8") (pin "2") (pinfunction "S1_2") (pintype "passive"))
      (node (ref "X1") (pin "GND") (pinfunction "GND_GND") (pintype "bidirectional"))
    )
    (net (code "41") (name "Net-(3V3-PadA)") (class "Default")
      (node (ref "3V3") (pin "A") (pinfunction "A_A") (pintype "passive"))
      (node (ref "R12V3") (pin "1") (pinfunction "1_1") (pintype "passive"))
    )
    (net (code "42") (name "Net-(5V-PadA)") (class "Default")
      (node (ref "5V") (pin "A") (pinfunction "A_A") (pintype "passive"))
      (node (ref "R12V2") (pin "1") (pinfunction "1_1") (pintype "passive"))
    )
    (net (code "43") (name "Net-(12V0-PadA)") (class "Default")
      (node (ref "12V0") (pin "A") (pinfunction "A_A") (pintype "passive"))
      (node (ref "R12V1") (pin "1") (pinfunction "1_1") (pintype "passive"))
    )
    (net (code "44") (name "Net-(ANT2-1)") (class "Default")
      (node (ref "ANT2") (pin "ANT") (pinfunction "1_ANT") (pintype "bidirectional"))
      (node (ref "C14") (pin "2") (pinfunction "C_2") (pintype "passive"))
      (node (ref "L4") (pin "1") (pinfunction "L_1") (pintype "passive"))
    )
    (net (code "45") (name "Net-(D_RL1-PadA)") (class "Default")
      (node (ref "D_RL1") (pin "A") (pinfunction "A_A") (pintype "passive"))
      (node (ref "K1") (pin "2") (pinfunction "2_2") (pintype "passive"))
      (node (ref "LED4") (pin "C") (pinfunction "C_C") (pintype "passive"))
      (node (ref "RL_Q1") (pin "C") (pinfunction "C_C") (pintype "passive"))
    )
    (net (code "46") (name "Net-(D_RL2-PadA)") (class "Default")
      (node (ref "D_RL2") (pin "A") (pinfunction "A_A") (pintype "passive"))
      (node (ref "K2") (pin "2") (pinfunction "2_2") (pintype "passive"))
      (node (ref "LED5") (pin "C") (pinfunction "C_C") (pintype "passive"))
      (node (ref "RL_Q2") (pin "C") (pinfunction "C_C") (pintype "passive"))
    )
    (net (code "47") (name "Net-(D_RL3-PadA)") (class "Default")
      (node (ref "D_RL3") (pin "A") (pinfunction "A_A") (pintype "passive"))
      (node (ref "K3") (pin "2") (pinfunction "2_2") (pintype "passive"))
      (node (ref "LED6") (pin "C") (pinfunction "C_C") (pintype "passive"))
      (node (ref "RL_Q3") (pin "C") (pinfunction "C_C") (pintype "passive"))
    )
    (net (code "48") (name "Net-(IC2-CLK)") (class "Default")
      (node (ref "IC2") (pin "6") (pinfunction "CLK_6") (pintype "bidirectional"))
      (node (ref "R5") (pin "1") (pinfunction "1_1") (pintype "passive"))
    )
    (net (code "49") (name "Net-(IC3-EE_CLK)") (class "Default")
      (node (ref "IC3") (pin "13") (pinfunction "EE_CLK_13") (pintype "bidirectional"))
      (node (ref "R10") (pin "2") (pinfunction "2_2") (pintype "passive"))
    )
    (net (code "50") (name "Net-(IC3-EE_DATA)") (class "Default")
      (node (ref "IC3") (pin "14") (pinfunction "EE_DATA_14") (pintype "bidirectional"))
      (node (ref "R11") (pin "2") (pinfunction "2_2") (pintype "passive"))
    )
    (net (code "51") (name "Net-(IC3-OSC1)") (class "Default")
      (node (ref "C2") (pin "1") (pinfunction "1_1") (pintype "passive"))
      (node (ref "CRYS1") (pin "2") (pinfunction "2_2") (pintype "passive"))
      (node (ref "IC3") (pin "27") (pinfunction "OSC1_27") (pintype "bidirectional"))
    )
    (net (code "52") (name "Net-(IC3-OSC2)") (class "Default")
      (node (ref "C1") (pin "1") (pinfunction "1_1") (pintype "passive"))
      (node (ref "CRYS1") (pin "1") (pinfunction "1_1") (pintype "passive"))
      (node (ref "IC3") (pin "28") (pinfunction "OSC2_28") (pintype "bidirectional"))
    )
    (net (code "53") (name "Net-(LED1-PadC)") (class "Default")
      (node (ref "LED1") (pin "C") (pinfunction "C_C") (pintype "passive"))
      (node (ref "R29") (pin "2") (pinfunction "2_2") (pintype "passive"))
    )
    (net (code "54") (name "Net-(LED2-PadC)") (class "Default")
      (node (ref "LED2") (pin "C") (pinfunction "C_C") (pintype "passive"))
      (node (ref "LED3") (pin "C") (pinfunction "C_C") (pintype "passive"))
      (node (ref "R9") (pin "2") (pinfunction "2_2") (pintype "passive"))
    )
    (net (code "55") (name "Net-(LED4-PadA)") (class "Default")
      (node (ref "LED4") (pin "A") (pinfunction "A_A") (pintype "passive"))
      (node (ref "R13") (pin "1") (pinfunction "1_1") (pintype "passive"))
    )
    (net (code "56") (name "Net-(LED5-PadA)") (class "Default")
      (node (ref "LED5") (pin "A") (pinfunction "A_A") (pintype "passive"))
      (node (ref "R24") (pin "1") (pinfunction "1_1") (pintype "passive"))
    )
    (net (code "57") (name "Net-(LED6-PadA)") (class "Default")
      (node (ref "LED6") (pin "A") (pinfunction "A_A") (pintype "passive"))
      (node (ref "R28") (pin "1") (pinfunction "1_1") (pintype "passive"))
    )
    (net (code "58") (name "Net-(OK1-EMIT)") (class "Default")
      (node (ref "OK1") (pin "3") (pinfunction "EMIT_3") (pintype "passive"))
      (node (ref "R2") (pin "2") (pinfunction "2_2") (pintype "passive"))
    )
    (net (code "59") (name "Net-(OK2-EMIT)") (class "Default")
      (node (ref "OK2") (pin "3") (pinfunction "EMIT_3") (pintype "passive"))
      (node (ref "R22") (pin "2") (pinfunction "2_2") (pintype "passive"))
    )
    (net (code "60") (name "Net-(OK3-EMIT)") (class "Default")
      (node (ref "OK3") (pin "3") (pinfunction "EMIT_3") (pintype "passive"))
      (node (ref "R26") (pin "2") (pinfunction "2_2") (pintype "passive"))
    )
    (net (code "61") (name "Net-(R1-Pad2)") (class "Default")
      (node (ref "R1") (pin "2") (pinfunction "2_2") (pintype "passive"))
      (node (ref "R2") (pin "1") (pinfunction "1_1") (pintype "passive"))
      (node (ref "RL_Q1") (pin "B") (pinfunction "B_B") (pintype "passive"))
    )
    (net (code "62") (name "Net-(R12-Pad1)") (class "Default")
      (node (ref "R12") (pin "1") (pinfunction "1_1") (pintype "passive"))
      (node (ref "X1") (pin "D-") (pinfunction "D-_D-") (pintype "bidirectional"))
    )
    (net (code "63") (name "Net-(R14-Pad1)") (class "Default")
      (node (ref "R14") (pin "1") (pinfunction "1_1") (pintype "passive"))
      (node (ref "X1") (pin "D+") (pinfunction "D+_D+") (pintype "bidirectional"))
    )
    (net (code "64") (name "Net-(R18-Pad2)") (class "Default")
      (node (ref "R18") (pin "2") (pinfunction "2_2") (pintype "passive"))
      (node (ref "T1") (pin "B") (pinfunction "B_B") (pintype "passive"))
    )
    (net (code "65") (name "Net-(R19-Pad2)") (class "Default")
      (node (ref "R19") (pin "2") (pinfunction "2_2") (pintype "passive"))
      (node (ref "T2") (pin "B") (pinfunction "B_B") (pintype "passive"))
    )
    (net (code "66") (name "Net-(R21-Pad2)") (class "Default")
      (node (ref "R21") (pin "2") (pinfunction "2_2") (pintype "passive"))
      (node (ref "R22") (pin "1") (pinfunction "1_1") (pintype "passive"))
      (node (ref "RL_Q2") (pin "B") (pinfunction "B_B") (pintype "passive"))
    )
    (net (code "67") (name "Net-(R25-Pad2)") (class "Default")
      (node (ref "R25") (pin "2") (pinfunction "2_2") (pintype "passive"))
      (node (ref "R26") (pin "1") (pinfunction "1_1") (pintype "passive"))
      (node (ref "RL_Q3") (pin "B") (pinfunction "B_B") (pintype "passive"))
    )
    (net (code "68") (name "Net-(U1-CHIP_EN)") (class "Default")
      (node (ref "R16") (pin "1") (pinfunction "1_1") (pintype "passive"))
      (node (ref "U1") (pin "7") (pinfunction "CHIP_EN_7") (pintype "bidirectional"))
    )
    (net (code "69") (name "Net-(U1-GPIO2)") (class "Default")
      (node (ref "R7") (pin "1") (pinfunction "1_1") (pintype "passive"))
      (node (ref "U1") (pin "14") (pinfunction "GPIO2_14") (pintype "bidirectional"))
    )
    (net (code "70") (name "Net-(U1-LNA)") (class "Default")
      (node (ref "C14") (pin "1") (pinfunction "C_1") (pintype "passive"))
      (node (ref "L3") (pin "1") (pinfunction "L_1") (pintype "passive"))
      (node (ref "U1") (pin "2") (pinfunction "LNA_2") (pintype "bidirectional"))
    )
    (net (code "71") (name "Net-(U1-MTDO{slash}SPICS{slash}GPIO15)") (class "Default")
      (node (ref "R6") (pin "1") (pinfunction "1_1") (pintype "passive"))
      (node (ref "U1") (pin "13") (pinfunction "MTDO/SPICS/GPIO15_13") (pintype "bidirectional"))
    )
    (net (code "72") (name "Net-(U1-RES12K)") (class "Default")
      (node (ref "R17") (pin "2") (pinfunction "2_2") (pintype "passive"))
      (node (ref "U1") (pin "31") (pinfunction "RES12K_31") (pintype "bidirectional"))
    )
    (net (code "73") (name "Net-(VPP_S1-S)") (class "Default")
      (node (ref "R8") (pin "1") (pinfunction "1_1") (pintype "passive"))
      (node (ref "T1") (pin "C") (pinfunction "C_C") (pintype "passive"))
      (node (ref "VPP_S1") (pin "1") (pinfunction "S_1") (pintype "passive"))
      (node (ref "VPP_S1") (pin "2") (pinfunction "S1_2") (pintype "passive"))
    )
    (net (code "74") (name "unconnected-(IC3-GP0-Pad22)") (class "Default")
      (node (ref "IC3") (pin "22") (pinfunction "GP0_22") (pintype "bidirectional"))
    )
    (net (code "75") (name "unconnected-(IC3-GP1-Pad23)") (class "Default")
      (node (ref "IC3") (pin "23") (pinfunction "GP1_23") (pintype "bidirectional"))
    )
    (net (code "76") (name "unconnected-(IC3-SHUTD-Pad12)") (class "Default")
      (node (ref "IC3") (pin "12") (pinfunction "SHUTD_12") (pintype "bidirectional"))
    )
    (net (code "77") (name "unconnected-(K1-PadO)") (class "Default")
      (node (ref "K1") (pin "O") (pinfunction "O_O") (pintype "passive"))
    )
    (net (code "78") (name "unconnected-(K2-PadO)") (class "Default")
      (node (ref "K2") (pin "O") (pinfunction "O_O") (pintype "passive"))
    )
    (net (code "79") (name "unconnected-(K3-PadO)") (class "Default")
      (node (ref "K3") (pin "O") (pinfunction "O_O") (pintype "passive"))
    )
    (net (code "80") (name "unconnected-(U1-VDD_RTC-Pad5)") (class "Default")
      (node (ref "U1") (pin "5") (pinfunction "VDD_RTC_5") (pintype "bidirectional"))
    )
  )
)
